# main.net
KiCad netlist of a schematic drawn in Altium Designer
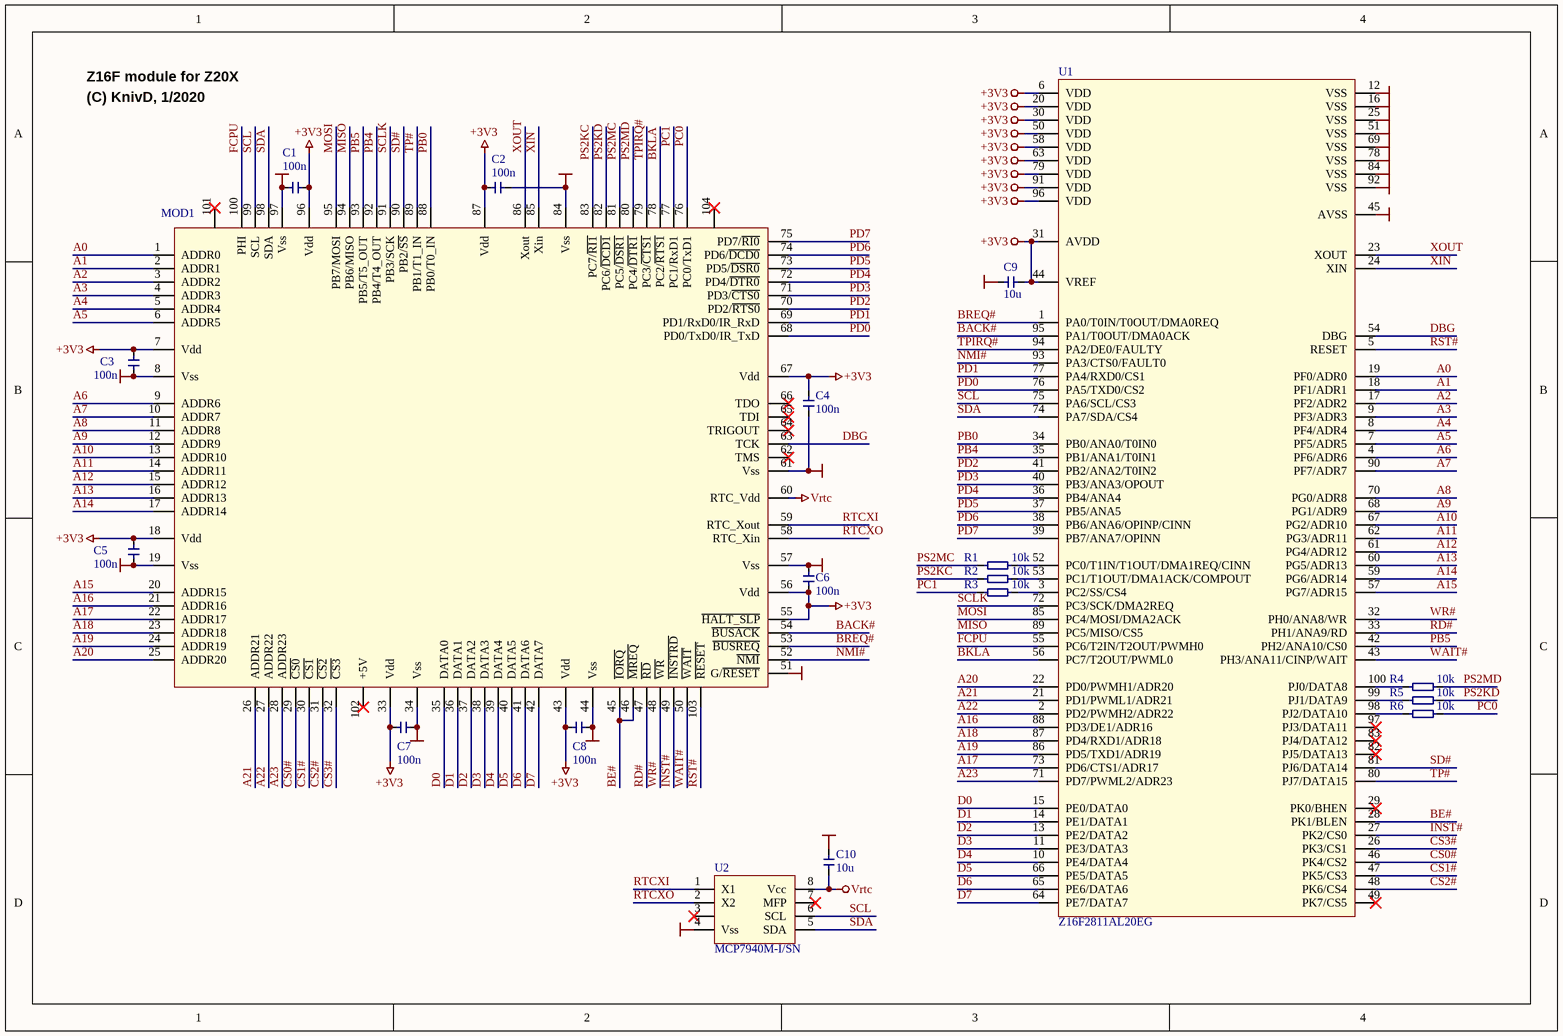
[diagram p0: main.SchDoc]

(export (version "E")
  (design (tool "Eeschema 10.0.6"))
  (components
    (comp (ref "C1")
      (value "100n")
      (footprint "_0805_CAP")
      (description "Capacitor")
      (libsource (lib "Discretes") (part "Capacitor"))
    )
    (comp (ref "C2")
      (value "100n")
      (footprint "_0805_CAP")
      (description "Capacitor")
      (libsource (lib "Discretes") (part "Capacitor"))
    )
    (comp (ref "C3")
      (value "100n")
      (footprint "_0805_CAP")
      (description "Capacitor")
      (libsource (lib "Discretes") (part "Capacitor"))
    )
    (comp (ref "C4")
      (value "100n")
      (footprint "_0805_CAP")
      (description "Capacitor")
      (libsource (lib "Discretes") (part "Capacitor"))
    )
    (comp (ref "C5")
      (value "100n")
      (footprint "_0805_CAP")
      (description "Capacitor")
      (libsource (lib "Discretes") (part "Capacitor"))
    )
    (comp (ref "C6")
      (value "100n")
      (footprint "_0805_CAP")
      (description "Capacitor")
      (libsource (lib "Discretes") (part "Capacitor"))
    )
    (comp (ref "C7")
      (value "100n")
      (footprint "_0805_CAP")
      (description "Capacitor")
      (libsource (lib "Discretes") (part "Capacitor"))
    )
    (comp (ref "C8")
      (value "100n")
      (footprint "_0805_CAP")
      (description "Capacitor")
      (libsource (lib "Discretes") (part "Capacitor"))
    )
    (comp (ref "C9")
      (value "10u")
      (footprint "_0805_CAP")
      (description "Capacitor")
      (libsource (lib "Discretes") (part "Capacitor"))
    )
    (comp (ref "C10")
      (value "10u")
      (footprint "_0805_CAP")
      (description "Capacitor")
      (libsource (lib "Discretes") (part "Capacitor"))
    )
    (comp (ref "MOD1")
      (value "Z20X CPU Module")
      (footprint "PGA100X15")
      (libsource (lib "Modules") (part "Z20X CPU Module"))
    )
    (comp (ref "R1")
      (value "10k")
      (footprint "_0805_RES")
      (description "Resistor")
      (libsource (lib "Discretes") (part "Resistor"))
    )
    (comp (ref "R2")
      (value "10k")
      (footprint "_0805_RES")
      (description "Resistor")
      (libsource (lib "Discretes") (part "Resistor"))
    )
    (comp (ref "R3")
      (value "10k")
      (footprint "_0805_RES")
      (description "Resistor")
      (libsource (lib "Discretes") (part "Resistor"))
    )
    (comp (ref "R4")
      (value "10k")
      (footprint "_0805_RES")
      (description "Resistor")
      (libsource (lib "Discretes") (part "Resistor"))
    )
    (comp (ref "R5")
      (value "10k")
      (footprint "_0805_RES")
      (description "Resistor")
      (libsource (lib "Discretes") (part "Resistor"))
    )
    (comp (ref "R6")
      (value "10k")
      (footprint "_0805_RES")
      (description "Resistor")
      (libsource (lib "Discretes") (part "Resistor"))
    )
    (comp (ref "U1")
      (value "Z16F2811AL20EG")
      (footprint "QFP50P1600X1600X170-100N")
      (description "16-bit microcontroller/microprocessor")
      (fields (field (name "MANUFACTURER") "Zilog"))
      (libsource (lib "IC Microcontrollers and Processors") (part "Z16F (QFP100)"))
    )
    (comp (ref "U2")
      (value "MCP7940M-I/SN")
      (footprint "SOIC8")
      (description "Low-Cost I2C™ Real-Time Clock/Calendar with SRAM")
      (fields (field (name "MANUFACTURER") "Microchip"))
      (libsource (lib "IC Other Functions") (part "MCP7940M"))
    )
  )
  (nets
    (net (code "1") (name "+3V3") (class "Default")
      (node (ref "C1") (pin "1") (pintype "passive"))
      (node (ref "C2") (pin "2") (pintype "passive"))
      (node (ref "C3") (pin "1") (pintype "passive"))
      (node (ref "C4") (pin "2") (pintype "passive"))
      (node (ref "C5") (pin "1") (pintype "passive"))
      (node (ref "C6") (pin "1") (pintype "passive"))
      (node (ref "C7") (pin "1") (pintype "passive"))
      (node (ref "C8") (pin "1") (pintype "passive"))
      (node (ref "C9") (pin "1") (pintype "passive"))
      (node (ref "MOD1") (pin "18") (pinfunction "Vdd_18") (pintype "passive"))
      (node (ref "MOD1") (pin "33") (pinfunction "Vdd_33") (pintype "passive"))
      (node (ref "MOD1") (pin "43") (pinfunction "Vdd_43") (pintype "passive"))
      (node (ref "MOD1") (pin "55") (pinfunction "~{HALT_SLP}_55") (pintype "passive"))
      (node (ref "MOD1") (pin "56") (pinfunction "Vdd_56") (pintype "passive"))
      (node (ref "MOD1") (pin "67") (pinfunction "Vdd_67") (pintype "passive"))
      (node (ref "MOD1") (pin "7") (pinfunction "Vdd_7") (pintype "passive"))
      (node (ref "MOD1") (pin "87") (pinfunction "Vdd_87") (pintype "passive"))
      (node (ref "MOD1") (pin "96") (pinfunction "Vdd_96") (pintype "passive"))
      (node (ref "U1") (pin "20") (pinfunction "VDD_20") (pintype "passive"))
      (node (ref "U1") (pin "30") (pinfunction "VDD_30") (pintype "passive"))
      (node (ref "U1") (pin "31") (pinfunction "AVDD_31") (pintype "passive"))
      (node (ref "U1") (pin "44") (pinfunction "VREF_44") (pintype "passive"))
      (node (ref "U1") (pin "50") (pinfunction "VDD_50") (pintype "passive"))
      (node (ref "U1") (pin "58") (pinfunction "VDD_58") (pintype "passive"))
      (node (ref "U1") (pin "6") (pinfunction "VDD_6") (pintype "passive"))
      (node (ref "U1") (pin "63") (pinfunction "VDD_63") (pintype "passive"))
      (node (ref "U1") (pin "79") (pinfunction "VDD_79") (pintype "passive"))
      (node (ref "U1") (pin "91") (pinfunction "VDD_91") (pintype "passive"))
      (node (ref "U1") (pin "96") (pinfunction "VDD_96") (pintype "passive"))
    )
    (net (code "2") (name "/A0") (class "Default")
      (node (ref "MOD1") (pin "1") (pinfunction "ADDR0_1") (pintype "passive"))
      (node (ref "U1") (pin "19") (pinfunction "PF0/ADR0_19") (pintype "passive"))
    )
    (net (code "3") (name "/A1") (class "Default")
      (node (ref "MOD1") (pin "2") (pinfunction "ADDR1_2") (pintype "passive"))
      (node (ref "U1") (pin "18") (pinfunction "PF1/ADR1_18") (pintype "passive"))
    )
    (net (code "4") (name "/A2") (class "Default")
      (node (ref "MOD1") (pin "3") (pinfunction "ADDR2_3") (pintype "passive"))
      (node (ref "U1") (pin "17") (pinfunction "PF2/ADR2_17") (pintype "passive"))
    )
    (net (code "5") (name "/A3") (class "Default")
      (node (ref "MOD1") (pin "4") (pinfunction "ADDR3_4") (pintype "passive"))
      (node (ref "U1") (pin "9") (pinfunction "PF3/ADR3_9") (pintype "passive"))
    )
    (net (code "6") (name "/A4") (class "Default")
      (node (ref "MOD1") (pin "5") (pinfunction "ADDR4_5") (pintype "passive"))
      (node (ref "U1") (pin "8") (pinfunction "PF4/ADR4_8") (pintype "passive"))
    )
    (net (code "7") (name "/A5") (class "Default")
      (node (ref "MOD1") (pin "6") (pinfunction "ADDR5_6") (pintype "passive"))
      (node (ref "U1") (pin "7") (pinfunction "PF5/ADR5_7") (pintype "passive"))
    )
    (net (code "8") (name "/A6") (class "Default")
      (node (ref "MOD1") (pin "9") (pinfunction "ADDR6_9") (pintype "passive"))
      (node (ref "U1") (pin "4") (pinfunction "PF6/ADR6_4") (pintype "passive"))
    )
    (net (code "9") (name "/A7") (class "Default")
      (node (ref "MOD1") (pin "10") (pinfunction "ADDR7_10") (pintype "passive"))
      (node (ref "U1") (pin "90") (pinfunction "PF7/ADR7_90") (pintype "passive"))
    )
    (net (code "10") (name "/A8") (class "Default")
      (node (ref "MOD1") (pin "11") (pinfunction "ADDR8_11") (pintype "passive"))
      (node (ref "U1") (pin "70") (pinfunction "PG0/ADR8_70") (pintype "passive"))
    )
    (net (code "11") (name "/A9") (class "Default")
      (node (ref "MOD1") (pin "12") (pinfunction "ADDR9_12") (pintype "passive"))
      (node (ref "U1") (pin "68") (pinfunction "PG1/ADR9_68") (pintype "passive"))
    )
    (net (code "12") (name "/A10") (class "Default")
      (node (ref "MOD1") (pin "13") (pinfunction "ADDR10_13") (pintype "passive"))
      (node (ref "U1") (pin "67") (pinfunction "PG2/ADR10_67") (pintype "passive"))
    )
    (net (code "13") (name "/A11") (class "Default")
      (node (ref "MOD1") (pin "14") (pinfunction "ADDR11_14") (pintype "passive"))
      (node (ref "U1") (pin "62") (pinfunction "PG3/ADR11_62") (pintype "passive"))
    )
    (net (code "14") (name "/A12") (class "Default")
      (node (ref "MOD1") (pin "15") (pinfunction "ADDR12_15") (pintype "passive"))
      (node (ref "U1") (pin "61") (pinfunction "PG4/ADR12_61") (pintype "passive"))
    )
    (net (code "15") (name "/A13") (class "Default")
      (node (ref "MOD1") (pin "16") (pinfunction "ADDR13_16") (pintype "passive"))
      (node (ref "U1") (pin "60") (pinfunction "PG5/ADR13_60") (pintype "passive"))
    )
    (net (code "16") (name "/A14") (class "Default")
      (node (ref "MOD1") (pin "17") (pinfunction "ADDR14_17") (pintype "passive"))
      (node (ref "U1") (pin "59") (pinfunction "PG6/ADR14_59") (pintype "passive"))
    )
    (net (code "17") (name "/A15") (class "Default")
      (node (ref "MOD1") (pin "20") (pinfunction "ADDR15_20") (pintype "passive"))
      (node (ref "U1") (pin "57") (pinfunction "PG7/ADR15_57") (pintype "passive"))
    )
    (net (code "18") (name "/A16") (class "Default")
      (node (ref "MOD1") (pin "21") (pinfunction "ADDR16_21") (pintype "passive"))
      (node (ref "U1") (pin "88") (pinfunction "PD3/DE1/ADR16_88") (pintype "passive"))
    )
    (net (code "19") (name "/A17") (class "Default")
      (node (ref "MOD1") (pin "22") (pinfunction "ADDR17_22") (pintype "passive"))
      (node (ref "U1") (pin "73") (pinfunction "PD6/CTS1/ADR17_73") (pintype "passive"))
    )
    (net (code "20") (name "/A18") (class "Default")
      (node (ref "MOD1") (pin "23") (pinfunction "ADDR18_23") (pintype "passive"))
      (node (ref "U1") (pin "87") (pinfunction "PD4/RXD1/ADR18_87") (pintype "passive"))
    )
    (net (code "21") (name "/A19") (class "Default")
      (node (ref "MOD1") (pin "24") (pinfunction "ADDR19_24") (pintype "passive"))
      (node (ref "U1") (pin "86") (pinfunction "PD5/TXD1/ADR19_86") (pintype "passive"))
    )
    (net (code "22") (name "/A20") (class "Default")
      (node (ref "MOD1") (pin "25") (pinfunction "ADDR20_25") (pintype "passive"))
      (node (ref "U1") (pin "22") (pinfunction "PD0/PWMH1/ADR20_22") (pintype "passive"))
    )
    (net (code "23") (name "/A21") (class "Default")
      (node (ref "MOD1") (pin "26") (pinfunction "ADDR21_26") (pintype "passive"))
      (node (ref "U1") (pin "21") (pinfunction "PD1/PWML1/ADR21_21") (pintype "passive"))
    )
    (net (code "24") (name "/A22") (class "Default")
      (node (ref "MOD1") (pin "27") (pinfunction "ADDR22_27") (pintype "passive"))
      (node (ref "U1") (pin "2") (pinfunction "PD2/PWMH2/ADR22_2") (pintype "passive"))
    )
    (net (code "25") (name "/A23") (class "Default")
      (node (ref "MOD1") (pin "28") (pinfunction "ADDR23_28") (pintype "passive"))
      (node (ref "U1") (pin "71") (pinfunction "PD7/PWML2/ADR23_71") (pintype "passive"))
    )
    (net (code "26") (name "/BACK#") (class "Default")
      (node (ref "MOD1") (pin "54") (pinfunction "~{BUSACK}_54") (pintype "passive"))
      (node (ref "U1") (pin "95") (pinfunction "PA1/T0OUT/DMA0ACK_95") (pintype "passive"))
    )
    (net (code "27") (name "/BE#") (class "Default")
      (node (ref "MOD1") (pin "45") (pinfunction "~{IORQ}_45") (pintype "passive"))
      (node (ref "MOD1") (pin "46") (pinfunction "~{MREQ}_46") (pintype "passive"))
      (node (ref "U1") (pin "28") (pinfunction "PK1/BLEN_28") (pintype "passive"))
    )
    (net (code "28") (name "/BKLA") (class "Default")
      (node (ref "MOD1") (pin "78") (pinfunction "PC2/~{RTS1}_78") (pintype "passive"))
      (node (ref "U1") (pin "56") (pinfunction "PC7/T2OUT/PWML0_56") (pintype "passive"))
    )
    (net (code "29") (name "/BREQ#") (class "Default")
      (node (ref "MOD1") (pin "53") (pinfunction "~{BUSREQ}_53") (pintype "passive"))
      (node (ref "U1") (pin "1") (pinfunction "PA0/T0IN/T0OUT/DMA0REQ_1") (pintype "passive"))
    )
    (net (code "30") (name "/CS0#") (class "Default")
      (node (ref "MOD1") (pin "29") (pinfunction "~{CS0}_29") (pintype "passive"))
      (node (ref "U1") (pin "46") (pinfunction "PK4/CS2_46") (pintype "passive"))
    )
    (net (code "31") (name "/CS1#") (class "Default")
      (node (ref "MOD1") (pin "30") (pinfunction "~{CS1}_30") (pintype "passive"))
      (node (ref "U1") (pin "47") (pinfunction "PK5/CS3_47") (pintype "passive"))
    )
    (net (code "32") (name "/CS2#") (class "Default")
      (node (ref "MOD1") (pin "31") (pinfunction "~{CS2}_31") (pintype "passive"))
      (node (ref "U1") (pin "48") (pinfunction "PK6/CS4_48") (pintype "passive"))
    )
    (net (code "33") (name "/CS3#") (class "Default")
      (node (ref "MOD1") (pin "32") (pinfunction "~{CS3}_32") (pintype "passive"))
      (node (ref "U1") (pin "26") (pinfunction "PK3/CS1_26") (pintype "passive"))
    )
    (net (code "34") (name "/D0") (class "Default")
      (node (ref "MOD1") (pin "35") (pinfunction "DATA0_35") (pintype "passive"))
      (node (ref "U1") (pin "15") (pinfunction "PE0/DATA0_15") (pintype "passive"))
    )
    (net (code "35") (name "/D1") (class "Default")
      (node (ref "MOD1") (pin "36") (pinfunction "DATA1_36") (pintype "passive"))
      (node (ref "U1") (pin "14") (pinfunction "PE1/DATA1_14") (pintype "passive"))
    )
    (net (code "36") (name "/D2") (class "Default")
      (node (ref "MOD1") (pin "37") (pinfunction "DATA2_37") (pintype "passive"))
      (node (ref "U1") (pin "13") (pinfunction "PE2/DATA2_13") (pintype "passive"))
    )
    (net (code "37") (name "/D3") (class "Default")
      (node (ref "MOD1") (pin "38") (pinfunction "DATA3_38") (pintype "passive"))
      (node (ref "U1") (pin "11") (pinfunction "PE3/DATA3_11") (pintype "passive"))
    )
    (net (code "38") (name "/D4") (class "Default")
      (node (ref "MOD1") (pin "39") (pinfunction "DATA4_39") (pintype "passive"))
      (node (ref "U1") (pin "10") (pinfunction "PE4/DATA4_10") (pintype "passive"))
    )
    (net (code "39") (name "/D5") (class "Default")
      (node (ref "MOD1") (pin "40") (pinfunction "DATA5_40") (pintype "passive"))
      (node (ref "U1") (pin "66") (pinfunction "PE5/DATA5_66") (pintype "passive"))
    )
    (net (code "40") (name "/D6") (class "Default")
      (node (ref "MOD1") (pin "41") (pinfunction "DATA6_41") (pintype "passive"))
      (node (ref "U1") (pin "65") (pinfunction "PE6/DATA6_65") (pintype "passive"))
    )
    (net (code "41") (name "/D7") (class "Default")
      (node (ref "MOD1") (pin "42") (pinfunction "DATA7_42") (pintype "passive"))
      (node (ref "U1") (pin "64") (pinfunction "PE7/DATA7_64") (pintype "passive"))
    )
    (net (code "42") (name "/DBG") (class "Default")
      (node (ref "MOD1") (pin "63") (pinfunction "TCK_63") (pintype "passive"))
      (node (ref "U1") (pin "54") (pinfunction "DBG_54") (pintype "passive"))
    )
    (net (code "43") (name "/FCPU") (class "Default")
      (node (ref "MOD1") (pin "100") (pinfunction "PHI_100") (pintype "passive"))
      (node (ref "U1") (pin "55") (pinfunction "PC6/T2IN/T2OUT/PWMH0_55") (pintype "passive"))
    )
    (net (code "44") (name "/INST#") (class "Default")
      (node (ref "MOD1") (pin "49") (pinfunction "~{INSTRD}_49") (pintype "passive"))
      (node (ref "U1") (pin "27") (pinfunction "PK2/CS0_27") (pintype "passive"))
    )
    (net (code "45") (name "/MISO") (class "Default")
      (node (ref "MOD1") (pin "94") (pinfunction "PB6/MISO_94") (pintype "passive"))
      (node (ref "U1") (pin "89") (pinfunction "PC5/MISO/CS5_89") (pintype "passive"))
    )
    (net (code "46") (name "/MOSI") (class "Default")
      (node (ref "MOD1") (pin "95") (pinfunction "PB7/MOSI_95") (pintype "passive"))
      (node (ref "U1") (pin "85") (pinfunction "PC4/MOSI/DMA2ACK_85") (pintype "passive"))
    )
    (net (code "47") (name "/NMI#") (class "Default")
      (node (ref "MOD1") (pin "52") (pinfunction "~{NMI}_52") (pintype "passive"))
      (node (ref "U1") (pin "93") (pinfunction "PA3/CTS0/FAULT0_93") (pintype "passive"))
    )
    (net (code "48") (name "/PB0") (class "Default")
      (node (ref "MOD1") (pin "88") (pinfunction "PB0/T0_IN_88") (pintype "passive"))
      (node (ref "U1") (pin "34") (pinfunction "PB0/ANA0/T0IN0_34") (pintype "passive"))
    )
    (net (code "49") (name "/PB4") (class "Default")
      (node (ref "MOD1") (pin "92") (pinfunction "PB4/T4_OUT_92") (pintype "passive"))
      (node (ref "U1") (pin "35") (pinfunction "PB1/ANA1/T0IN1_35") (pintype "passive"))
    )
    (net (code "50") (name "/PB5") (class "Default")
      (node (ref "MOD1") (pin "93") (pinfunction "PB5/T5_OUT_93") (pintype "passive"))
      (node (ref "U1") (pin "42") (pinfunction "PH2/ANA10/CS0_42") (pintype "passive"))
    )
    (net (code "51") (name "/PC0") (class "Default")
      (node (ref "MOD1") (pin "76") (pinfunction "PC0/TxD1_76") (pintype "passive"))
      (node (ref "R6") (pin "1") (pintype "passive"))
    )
    (net (code "52") (name "/PC1") (class "Default")
      (node (ref "MOD1") (pin "77") (pinfunction "PC1/RxD1_77") (pintype "passive"))
      (node (ref "R3") (pin "2") (pintype "passive"))
    )
    (net (code "53") (name "/PD0") (class "Default")
      (node (ref "MOD1") (pin "68") (pinfunction "PD0/TxD0/IR_TxD_68") (pintype "passive"))
      (node (ref "U1") (pin "76") (pinfunction "PA5/TXD0/CS2_76") (pintype "passive"))
    )
    (net (code "54") (name "/PD1") (class "Default")
      (node (ref "MOD1") (pin "69") (pinfunction "PD1/RxD0/IR_RxD_69") (pintype "passive"))
      (node (ref "U1") (pin "77") (pinfunction "PA4/RXD0/CS1_77") (pintype "passive"))
    )
    (net (code "55") (name "/PD2") (class "Default")
      (node (ref "MOD1") (pin "70") (pinfunction "PD2/~{RTS0}_70") (pintype "passive"))
      (node (ref "U1") (pin "41") (pinfunction "PB2/ANA2/T0IN2_41") (pintype "passive"))
    )
    (net (code "56") (name "/PD3") (class "Default")
      (node (ref "MOD1") (pin "71") (pinfunction "PD3/~{CTS0}_71") (pintype "passive"))
      (node (ref "U1") (pin "40") (pinfunction "PB3/ANA3/OPOUT_40") (pintype "passive"))
    )
    (net (code "57") (name "/PD4") (class "Default")
      (node (ref "MOD1") (pin "72") (pinfunction "PD4/~{DTR0}_72") (pintype "passive"))
      (node (ref "U1") (pin "36") (pinfunction "PB4/ANA4_36") (pintype "passive"))
    )
    (net (code "58") (name "/PD5") (class "Default")
      (node (ref "MOD1") (pin "73") (pinfunction "PD5/~{DSR0}_73") (pintype "passive"))
      (node (ref "U1") (pin "37") (pinfunction "PB5/ANA5_37") (pintype "passive"))
    )
    (net (code "59") (name "/PD6") (class "Default")
      (node (ref "MOD1") (pin "74") (pinfunction "PD6/~{DCD0}_74") (pintype "passive"))
      (node (ref "U1") (pin "38") (pinfunction "PB6/ANA6/OPINP/CINN_38") (pintype "passive"))
    )
    (net (code "60") (name "/PD7") (class "Default")
      (node (ref "MOD1") (pin "75") (pinfunction "PD7/~{RI0}_75") (pintype "passive"))
      (node (ref "U1") (pin "39") (pinfunction "PB7/ANA7/OPINN_39") (pintype "passive"))
    )
    (net (code "61") (name "/PS2KC") (class "Default")
      (node (ref "MOD1") (pin "83") (pinfunction "PC7/~{RI1}_83") (pintype "passive"))
      (node (ref "R2") (pin "2") (pintype "passive"))
    )
    (net (code "62") (name "/PS2KD") (class "Default")
      (node (ref "MOD1") (pin "82") (pinfunction "PC6/~{DCD1}_82") (pintype "passive"))
      (node (ref "R5") (pin "1") (pintype "passive"))
    )
    (net (code "63") (name "/PS2MC") (class "Default")
      (node (ref "MOD1") (pin "81") (pinfunction "PC5/~{DSR1}_81") (pintype "passive"))
      (node (ref "R1") (pin "2") (pintype "passive"))
    )
    (net (code "64") (name "/PS2MD") (class "Default")
      (node (ref "MOD1") (pin "80") (pinfunction "PC4/~{DTR1}_80") (pintype "passive"))
      (node (ref "R4") (pin "1") (pintype "passive"))
    )
    (net (code "65") (name "/RD#") (class "Default")
      (node (ref "MOD1") (pin "47") (pinfunction "~{RD}_47") (pintype "passive"))
      (node (ref "U1") (pin "33") (pinfunction "PH1/ANA9/RD_33") (pintype "passive"))
    )
    (net (code "66") (name "/RST#") (class "Default")
      (node (ref "MOD1") (pin "103") (pinfunction "~{RESET}_103") (pintype "passive"))
      (node (ref "U1") (pin "5") (pinfunction "RESET_5") (pintype "passive"))
    )
    (net (code "67") (name "/RTCXI") (class "Default")
      (node (ref "MOD1") (pin "59") (pinfunction "RTC_Xout_59") (pintype "passive"))
      (node (ref "U2") (pin "1") (pinfunction "X1_1") (pintype "passive"))
    )
    (net (code "68") (name "/RTCXO") (class "Default")
      (node (ref "MOD1") (pin "58") (pinfunction "RTC_Xin_58") (pintype "passive"))
      (node (ref "U2") (pin "2") (pinfunction "X2_2") (pintype "passive"))
    )
    (net (code "69") (name "/SCL") (class "Default")
      (node (ref "MOD1") (pin "99") (pinfunction "SCL_99") (pintype "passive"))
      (node (ref "U1") (pin "75") (pinfunction "PA6/SCL/CS3_75") (pintype "passive"))
      (node (ref "U2") (pin "6") (pinfunction "SCL_6") (pintype "passive"))
    )
    (net (code "70") (name "/SCLK") (class "Default")
      (node (ref "MOD1") (pin "91") (pinfunction "PB3/SCK_91") (pintype "passive"))
      (node (ref "U1") (pin "72") (pinfunction "PC3/SCK/DMA2REQ_72") (pintype "passive"))
    )
    (net (code "71") (name "/SD#") (class "Default")
      (node (ref "MOD1") (pin "90") (pinfunction "PB2/~{SS}_90") (pintype "passive"))
      (node (ref "U1") (pin "81") (pinfunction "PJ6/DATA14_81") (pintype "passive"))
    )
    (net (code "72") (name "/SDA") (class "Default")
      (node (ref "MOD1") (pin "98") (pinfunction "SDA_98") (pintype "passive"))
      (node (ref "U1") (pin "74") (pinfunction "PA7/SDA/CS4_74") (pintype "passive"))
      (node (ref "U2") (pin "5") (pinfunction "SDA_5") (pintype "passive"))
    )
    (net (code "73") (name "/TP#") (class "Default")
      (node (ref "MOD1") (pin "89") (pinfunction "PB1/T1_IN_89") (pintype "passive"))
      (node (ref "U1") (pin "80") (pinfunction "PJ7/DATA15_80") (pintype "passive"))
    )
    (net (code "74") (name "/TPIRQ#") (class "Default")
      (node (ref "MOD1") (pin "79") (pinfunction "PC3/~{CTS1}_79") (pintype "passive"))
      (node (ref "U1") (pin "94") (pinfunction "PA2/DE0/FAULTY_94") (pintype "passive"))
    )
    (net (code "75") (name "/WAIT#") (class "Default")
      (node (ref "MOD1") (pin "50") (pinfunction "~{WAIT}_50") (pintype "passive"))
      (node (ref "U1") (pin "43") (pinfunction "PH3/ANA11/CINP/WAIT_43") (pintype "passive"))
    )
    (net (code "76") (name "/WR#") (class "Default")
      (node (ref "MOD1") (pin "48") (pinfunction "~{WR}_48") (pintype "passive"))
      (node (ref "U1") (pin "32") (pinfunction "PH0/ANA8/WR_32") (pintype "passive"))
    )
    (net (code "77") (name "/XIN") (class "Default")
      (node (ref "MOD1") (pin "85") (pinfunction "Xin_85") (pintype "passive"))
      (node (ref "U1") (pin "24") (pinfunction "XIN_24") (pintype "passive"))
    )
    (net (code "78") (name "/XOUT") (class "Default")
      (node (ref "MOD1") (pin "86") (pinfunction "Xout_86") (pintype "passive"))
      (node (ref "U1") (pin "23") (pinfunction "XOUT_23") (pintype "passive"))
    )
    (net (code "79") (name "GND") (class "Default")
      (node (ref "C1") (pin "2") (pintype "passive"))
      (node (ref "C10") (pin "1") (pintype "passive"))
      (node (ref "C2") (pin "1") (pintype "passive"))
      (node (ref "C3") (pin "2") (pintype "passive"))
      (node (ref "C4") (pin "1") (pintype "passive"))
      (node (ref "C5") (pin "2") (pintype "passive"))
      (node (ref "C6") (pin "2") (pintype "passive"))
      (node (ref "C7") (pin "2") (pintype "passive"))
      (node (ref "C8") (pin "2") (pintype "passive"))
      (node (ref "C9") (pin "2") (pintype "passive"))
      (node (ref "MOD1") (pin "19") (pinfunction "Vss_19") (pintype "passive"))
      (node (ref "MOD1") (pin "34") (pinfunction "Vss_34") (pintype "passive"))
      (node (ref "MOD1") (pin "44") (pinfunction "Vss_44") (pintype "passive"))
      (node (ref "MOD1") (pin "51") (pinfunction "G/~{RESET}_51") (pintype "passive"))
      (node (ref "MOD1") (pin "57") (pinfunction "Vss_57") (pintype "passive"))
      (node (ref "MOD1") (pin "61") (pinfunction "Vss_61") (pintype "passive"))
      (node (ref "MOD1") (pin "8") (pinfunction "Vss_8") (pintype "passive"))
      (node (ref "MOD1") (pin "84") (pinfunction "Vss_84") (pintype "passive"))
      (node (ref "MOD1") (pin "97") (pinfunction "Vss_97") (pintype "passive"))
      (node (ref "U1") (pin "12") (pinfunction "VSS_12") (pintype "passive"))
      (node (ref "U1") (pin "16") (pinfunction "VSS_16") (pintype "passive"))
      (node (ref "U1") (pin "25") (pinfunction "VSS_25") (pintype "passive"))
      (node (ref "U1") (pin "45") (pinfunction "AVSS_45") (pintype "passive"))
      (node (ref "U1") (pin "51") (pinfunction "VSS_51") (pintype "passive"))
      (node (ref "U1") (pin "69") (pinfunction "VSS_69") (pintype "passive"))
      (node (ref "U1") (pin "78") (pinfunction "VSS_78") (pintype "passive"))
      (node (ref "U1") (pin "84") (pinfunction "VSS_84") (pintype "passive"))
      (node (ref "U1") (pin "92") (pinfunction "VSS_92") (pintype "passive"))
      (node (ref "U2") (pin "4") (pinfunction "Vss_4") (pintype "passive"))
    )
    (net (code "80") (name "Net-(U1-PC0{slash}T1IN{slash}T1OUT{slash}DMA1REQ{slash}CINN)") (class "Default")
      (node (ref "R1") (pin "1") (pintype "passive"))
      (node (ref "U1") (pin "52") (pinfunction "PC0/T1IN/T1OUT/DMA1REQ/CINN_52") (pintype "passive"))
    )
    (net (code "81") (name "Net-(U1-PC1{slash}T1OUT{slash}DMA1ACK{slash}COMPOUT)") (class "Default")
      (node (ref "R2") (pin "1") (pintype "passive"))
      (node (ref "U1") (pin "53") (pinfunction "PC1/T1OUT/DMA1ACK/COMPOUT_53") (pintype "passive"))
    )
    (net (code "82") (name "Net-(U1-PC2{slash}SS{slash}CS4)") (class "Default")
      (node (ref "R3") (pin "1") (pintype "passive"))
      (node (ref "U1") (pin "3") (pinfunction "PC2/SS/CS4_3") (pintype "passive"))
    )
    (net (code "83") (name "Net-(U1-PJ0{slash}DATA8)") (class "Default")
      (node (ref "R4") (pin "2") (pintype "passive"))
      (node (ref "U1") (pin "100") (pinfunction "PJ0/DATA8_100") (pintype "passive"))
    )
    (net (code "84") (name "Net-(U1-PJ1{slash}DATA9)") (class "Default")
      (node (ref "R5") (pin "2") (pintype "passive"))
      (node (ref "U1") (pin "99") (pinfunction "PJ1/DATA9_99") (pintype "passive"))
    )
    (net (code "85") (name "Net-(U1-PJ2{slash}DATA10)") (class "Default")
      (node (ref "R6") (pin "2") (pintype "passive"))
      (node (ref "U1") (pin "98") (pinfunction "PJ2/DATA10_98") (pintype "passive"))
    )
    (net (code "86") (name "Vrtc") (class "Default")
      (node (ref "C10") (pin "2") (pintype "passive"))
      (node (ref "MOD1") (pin "60") (pinfunction "RTC_Vdd_60") (pintype "passive"))
      (node (ref "U2") (pin "8") (pinfunction "Vcc_8") (pintype "passive"))
    )
    (net (code "87") (name "unconnected-(MOD1-+5V-Pad102)") (class "Default")
      (node (ref "MOD1") (pin "102") (pinfunction "+5V_102") (pintype "passive+no_connect"))
    )
    (net (code "88") (name "unconnected-(MOD1-Pad101)") (class "Default")
      (node (ref "MOD1") (pin "101") (pintype "passive+no_connect"))
    )
    (net (code "89") (name "unconnected-(MOD1-Pad104)") (class "Default")
      (node (ref "MOD1") (pin "104") (pintype "passive+no_connect"))
    )
    (net (code "90") (name "unconnected-(MOD1-TDI-Pad65)") (class "Default")
      (node (ref "MOD1") (pin "65") (pinfunction "TDI_65") (pintype "passive+no_connect"))
    )
    (net (code "91") (name "unconnected-(MOD1-TDO-Pad66)") (class "Default")
      (node (ref "MOD1") (pin "66") (pinfunction "TDO_66") (pintype "passive+no_connect"))
    )
    (net (code "92") (name "unconnected-(MOD1-TMS-Pad62)") (class "Default")
      (node (ref "MOD1") (pin "62") (pinfunction "TMS_62") (pintype "passive+no_connect"))
    )
    (net (code "93") (name "unconnected-(MOD1-TRIGOUT-Pad64)") (class "Default")
      (node (ref "MOD1") (pin "64") (pinfunction "TRIGOUT_64") (pintype "passive+no_connect"))
    )
    (net (code "94") (name "unconnected-(U1-PJ3{slash}DATA11-Pad97)") (class "Default")
      (node (ref "U1") (pin "97") (pinfunction "PJ3/DATA11_97") (pintype "passive+no_connect"))
    )
    (net (code "95") (name "unconnected-(U1-PJ4{slash}DATA12-Pad83)") (class "Default")
      (node (ref "U1") (pin "83") (pinfunction "PJ4/DATA12_83") (pintype "passive+no_connect"))
    )
    (net (code "96") (name "unconnected-(U1-PJ5{slash}DATA13-Pad82)") (class "Default")
      (node (ref "U1") (pin "82") (pinfunction "PJ5/DATA13_82") (pintype "passive+no_connect"))
    )
    (net (code "97") (name "unconnected-(U1-PK0{slash}BHEN-Pad29)") (class "Default")
      (node (ref "U1") (pin "29") (pinfunction "PK0/BHEN_29") (pintype "passive+no_connect"))
    )
    (net (code "98") (name "unconnected-(U1-PK7{slash}CS5-Pad49)") (class "Default")
      (node (ref "U1") (pin "49") (pinfunction "PK7/CS5_49") (pintype "passive+no_connect"))
    )
    (net (code "99") (name "unconnected-(U2-MFP-Pad7)") (class "Default")
      (node (ref "U2") (pin "7") (pinfunction "MFP_7") (pintype "passive+no_connect"))
    )
    (net (code "100") (name "unconnected-(U2-Pad3)") (class "Default")
      (node (ref "U2") (pin "3") (pintype "passive+no_connect"))
    )
  )
)
